# SCH_Piano_touch_sensor_2021-10-13.net
KiCad netlist of a schematic drawn in EasyEDA
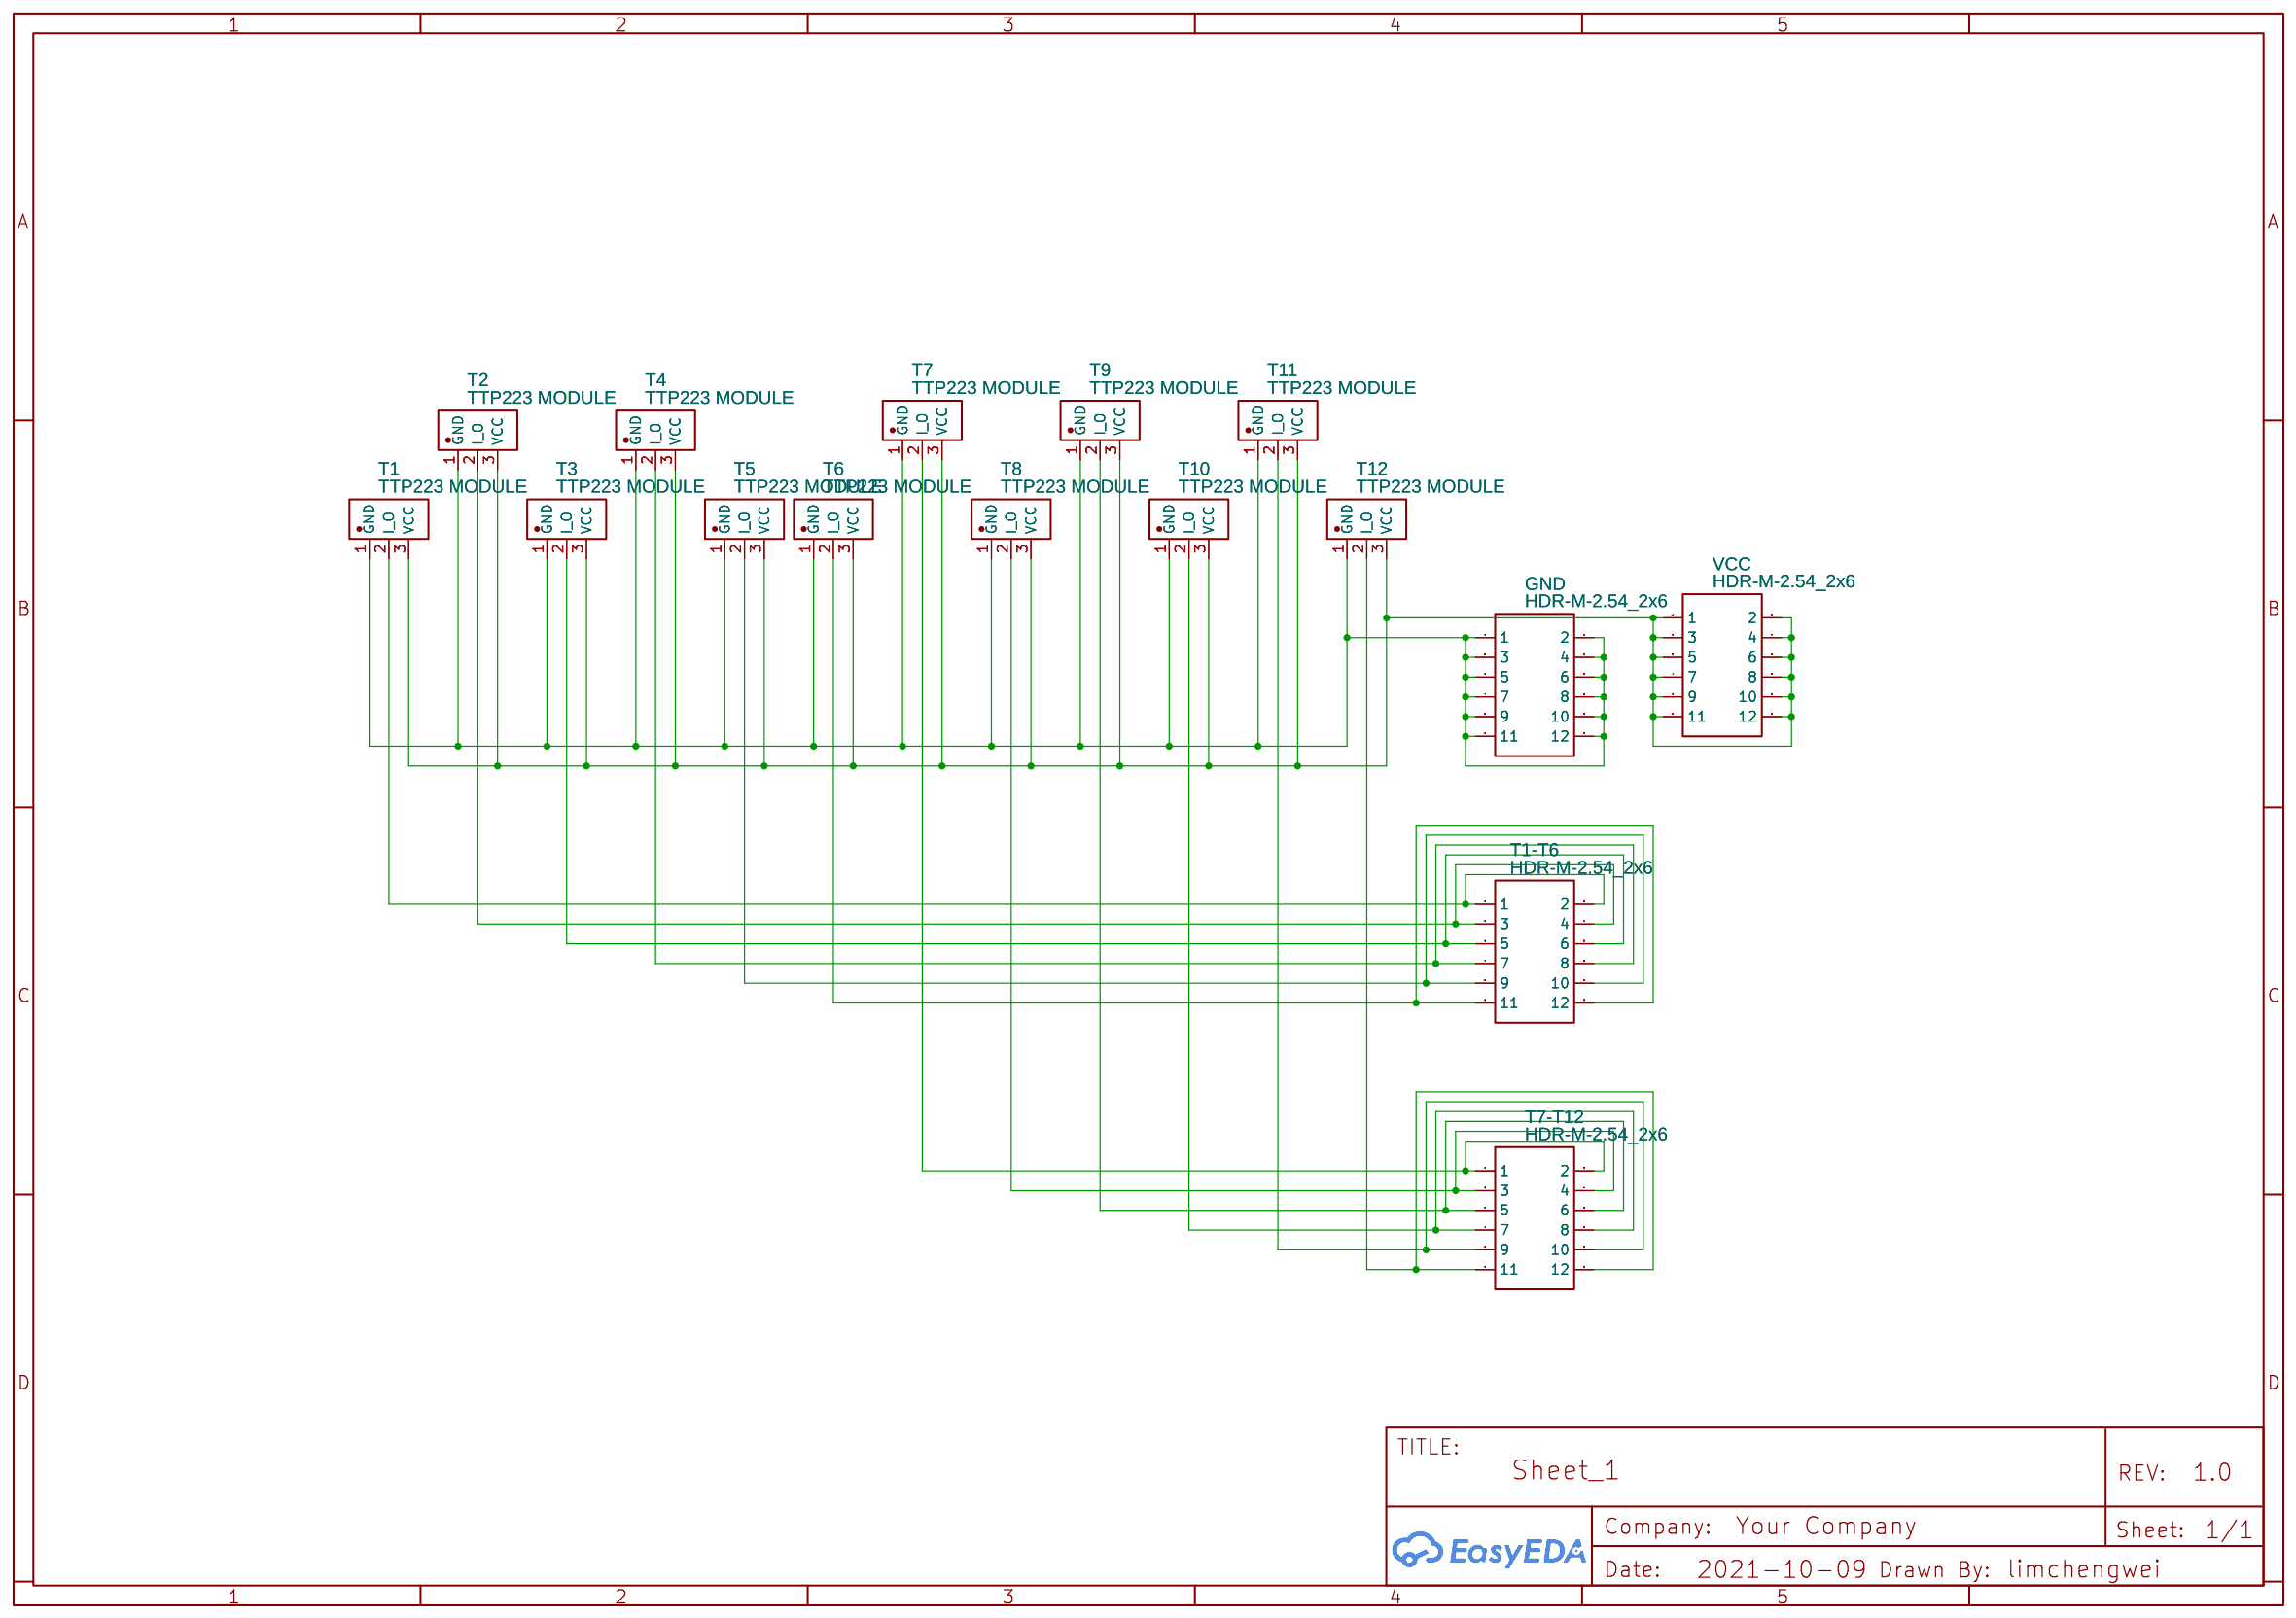
[diagram p0: schematic sheet]

(export (version "E")
  (design (tool "Eeschema 10.0.6"))
  (components
    (comp (ref "GND")
      (value "HDR-M-2.54_2x6")
      (fields (field (name "BOM_Supplier Part") "C124388"))
      (libsource (lib "") (part "HDR-M-2.54_2x6_3"))
    )
    (comp (ref "T1")
      (value "TTP223 MODULE")
      (fields
        (field (name "BOM_Manufacturer Part") "WJ2EDGVC-5.08-3P")
        (field (name "BOM_Supplier Part") "C8430")
      )
      (libsource (lib "") (part "TTP223 MODULE"))
    )
    (comp (ref "T1-T6")
      (value "HDR-M-2.54_2x6")
      (fields (field (name "BOM_Supplier Part") "C124388"))
      (libsource (lib "") (part "HDR-M-2.54_2x6_2"))
    )
    (comp (ref "T2")
      (value "TTP223 MODULE")
      (fields
        (field (name "BOM_Manufacturer Part") "WJ2EDGVC-5.08-3P")
        (field (name "BOM_Supplier Part") "C8430")
      )
      (libsource (lib "") (part "TTP223 MODULE"))
    )
    (comp (ref "T3")
      (value "TTP223 MODULE")
      (fields
        (field (name "BOM_Manufacturer Part") "WJ2EDGVC-5.08-3P")
        (field (name "BOM_Supplier Part") "C8430")
      )
      (libsource (lib "") (part "TTP223 MODULE"))
    )
    (comp (ref "T4")
      (value "TTP223 MODULE")
      (fields
        (field (name "BOM_Manufacturer Part") "WJ2EDGVC-5.08-3P")
        (field (name "BOM_Supplier Part") "C8430")
      )
      (libsource (lib "") (part "TTP223 MODULE"))
    )
    (comp (ref "T5")
      (value "TTP223 MODULE")
      (fields
        (field (name "BOM_Manufacturer Part") "WJ2EDGVC-5.08-3P")
        (field (name "BOM_Supplier Part") "C8430")
      )
      (libsource (lib "") (part "TTP223 MODULE"))
    )
    (comp (ref "T6")
      (value "TTP223 MODULE")
      (fields
        (field (name "BOM_Manufacturer Part") "WJ2EDGVC-5.08-3P")
        (field (name "BOM_Supplier Part") "C8430")
      )
      (libsource (lib "") (part "TTP223 MODULE"))
    )
    (comp (ref "T7")
      (value "TTP223 MODULE")
      (fields
        (field (name "BOM_Manufacturer Part") "WJ2EDGVC-5.08-3P")
        (field (name "BOM_Supplier Part") "C8430")
      )
      (libsource (lib "") (part "TTP223 MODULE"))
    )
    (comp (ref "T7-T12")
      (value "HDR-M-2.54_2x6")
      (fields (field (name "BOM_Supplier Part") "C124388"))
      (libsource (lib "") (part "HDR-M-2.54_2x6"))
    )
    (comp (ref "T8")
      (value "TTP223 MODULE")
      (fields
        (field (name "BOM_Manufacturer Part") "WJ2EDGVC-5.08-3P")
        (field (name "BOM_Supplier Part") "C8430")
      )
      (libsource (lib "") (part "TTP223 MODULE"))
    )
    (comp (ref "T9")
      (value "TTP223 MODULE")
      (fields
        (field (name "BOM_Manufacturer Part") "WJ2EDGVC-5.08-3P")
        (field (name "BOM_Supplier Part") "C8430")
      )
      (libsource (lib "") (part "TTP223 MODULE"))
    )
    (comp (ref "T10")
      (value "TTP223 MODULE")
      (fields
        (field (name "BOM_Manufacturer Part") "WJ2EDGVC-5.08-3P")
        (field (name "BOM_Supplier Part") "C8430")
      )
      (libsource (lib "") (part "TTP223 MODULE"))
    )
    (comp (ref "T11")
      (value "TTP223 MODULE")
      (fields
        (field (name "BOM_Manufacturer Part") "WJ2EDGVC-5.08-3P")
        (field (name "BOM_Supplier Part") "C8430")
      )
      (libsource (lib "") (part "TTP223 MODULE"))
    )
    (comp (ref "T12")
      (value "TTP223 MODULE")
      (fields
        (field (name "BOM_Manufacturer Part") "WJ2EDGVC-5.08-3P")
        (field (name "BOM_Supplier Part") "C8430")
      )
      (libsource (lib "") (part "TTP223 MODULE"))
    )
    (comp (ref "VCC")
      (value "HDR-M-2.54_2x6")
      (fields (field (name "BOM_Supplier Part") "C124388"))
      (libsource (lib "") (part "HDR-M-2.54_2x6_1"))
    )
  )
  (nets
    (net (code "1") (name "Net-(T1-GND)") (class "Default")
      (node (ref "GND") (pin "1") (pinfunction "1_1") (pintype "unspecified"))
      (node (ref "GND") (pin "10") (pinfunction "10_10") (pintype "unspecified"))
      (node (ref "GND") (pin "11") (pinfunction "11_11") (pintype "unspecified"))
      (node (ref "GND") (pin "12") (pinfunction "12_12") (pintype "unspecified"))
      (node (ref "GND") (pin "2") (pinfunction "2_2") (pintype "unspecified"))
      (node (ref "GND") (pin "3") (pinfunction "3_3") (pintype "unspecified"))
      (node (ref "GND") (pin "4") (pinfunction "4_4") (pintype "unspecified"))
      (node (ref "GND") (pin "5") (pinfunction "5_5") (pintype "unspecified"))
      (node (ref "GND") (pin "6") (pinfunction "6_6") (pintype "unspecified"))
      (node (ref "GND") (pin "7") (pinfunction "7_7") (pintype "unspecified"))
      (node (ref "GND") (pin "8") (pinfunction "8_8") (pintype "unspecified"))
      (node (ref "GND") (pin "9") (pinfunction "9_9") (pintype "unspecified"))
      (node (ref "T1") (pin "1") (pinfunction "GND_1") (pintype "unspecified"))
      (node (ref "T10") (pin "1") (pinfunction "GND_1") (pintype "unspecified"))
      (node (ref "T11") (pin "1") (pinfunction "GND_1") (pintype "unspecified"))
      (node (ref "T12") (pin "1") (pinfunction "GND_1") (pintype "unspecified"))
      (node (ref "T2") (pin "1") (pinfunction "GND_1") (pintype "unspecified"))
      (node (ref "T3") (pin "1") (pinfunction "GND_1") (pintype "unspecified"))
      (node (ref "T4") (pin "1") (pinfunction "GND_1") (pintype "unspecified"))
      (node (ref "T5") (pin "1") (pinfunction "GND_1") (pintype "unspecified"))
      (node (ref "T6") (pin "1") (pinfunction "GND_1") (pintype "unspecified"))
      (node (ref "T7") (pin "1") (pinfunction "GND_1") (pintype "unspecified"))
      (node (ref "T8") (pin "1") (pinfunction "GND_1") (pintype "unspecified"))
      (node (ref "T9") (pin "1") (pinfunction "GND_1") (pintype "unspecified"))
    )
    (net (code "2") (name "Net-(T1-I_O)") (class "Default")
      (node (ref "T1") (pin "2") (pinfunction "I_O_2") (pintype "unspecified"))
      (node (ref "T1-T6") (pin "1") (pinfunction "1_1") (pintype "unspecified"))
      (node (ref "T1-T6") (pin "2") (pinfunction "2_2") (pintype "unspecified"))
    )
    (net (code "3") (name "Net-(T1-VCC)") (class "Default")
      (node (ref "T1") (pin "3") (pinfunction "VCC_3") (pintype "unspecified"))
      (node (ref "T10") (pin "3") (pinfunction "VCC_3") (pintype "unspecified"))
      (node (ref "T11") (pin "3") (pinfunction "VCC_3") (pintype "unspecified"))
      (node (ref "T12") (pin "3") (pinfunction "VCC_3") (pintype "unspecified"))
      (node (ref "T2") (pin "3") (pinfunction "VCC_3") (pintype "unspecified"))
      (node (ref "T3") (pin "3") (pinfunction "VCC_3") (pintype "unspecified"))
      (node (ref "T4") (pin "3") (pinfunction "VCC_3") (pintype "unspecified"))
      (node (ref "T5") (pin "3") (pinfunction "VCC_3") (pintype "unspecified"))
      (node (ref "T6") (pin "3") (pinfunction "VCC_3") (pintype "unspecified"))
      (node (ref "T7") (pin "3") (pinfunction "VCC_3") (pintype "unspecified"))
      (node (ref "T8") (pin "3") (pinfunction "VCC_3") (pintype "unspecified"))
      (node (ref "T9") (pin "3") (pinfunction "VCC_3") (pintype "unspecified"))
      (node (ref "VCC") (pin "1") (pinfunction "1_1") (pintype "unspecified"))
      (node (ref "VCC") (pin "10") (pinfunction "10_10") (pintype "unspecified"))
      (node (ref "VCC") (pin "11") (pinfunction "11_11") (pintype "unspecified"))
      (node (ref "VCC") (pin "12") (pinfunction "12_12") (pintype "unspecified"))
      (node (ref "VCC") (pin "2") (pinfunction "2_2") (pintype "unspecified"))
      (node (ref "VCC") (pin "3") (pinfunction "3_3") (pintype "unspecified"))
      (node (ref "VCC") (pin "4") (pinfunction "4_4") (pintype "unspecified"))
      (node (ref "VCC") (pin "5") (pinfunction "5_5") (pintype "unspecified"))
      (node (ref "VCC") (pin "6") (pinfunction "6_6") (pintype "unspecified"))
      (node (ref "VCC") (pin "7") (pinfunction "7_7") (pintype "unspecified"))
      (node (ref "VCC") (pin "8") (pinfunction "8_8") (pintype "unspecified"))
      (node (ref "VCC") (pin "9") (pinfunction "9_9") (pintype "unspecified"))
    )
    (net (code "4") (name "Net-(T2-I_O)") (class "Default")
      (node (ref "T1-T6") (pin "3") (pinfunction "3_3") (pintype "unspecified"))
      (node (ref "T1-T6") (pin "4") (pinfunction "4_4") (pintype "unspecified"))
      (node (ref "T2") (pin "2") (pinfunction "I_O_2") (pintype "unspecified"))
    )
    (net (code "5") (name "Net-(T3-I_O)") (class "Default")
      (node (ref "T1-T6") (pin "5") (pinfunction "5_5") (pintype "unspecified"))
      (node (ref "T1-T6") (pin "6") (pinfunction "6_6") (pintype "unspecified"))
      (node (ref "T3") (pin "2") (pinfunction "I_O_2") (pintype "unspecified"))
    )
    (net (code "6") (name "Net-(T4-I_O)") (class "Default")
      (node (ref "T1-T6") (pin "7") (pinfunction "7_7") (pintype "unspecified"))
      (node (ref "T1-T6") (pin "8") (pinfunction "8_8") (pintype "unspecified"))
      (node (ref "T4") (pin "2") (pinfunction "I_O_2") (pintype "unspecified"))
    )
    (net (code "7") (name "Net-(T5-I_O)") (class "Default")
      (node (ref "T1-T6") (pin "10") (pinfunction "10_10") (pintype "unspecified"))
      (node (ref "T1-T6") (pin "9") (pinfunction "9_9") (pintype "unspecified"))
      (node (ref "T5") (pin "2") (pinfunction "I_O_2") (pintype "unspecified"))
    )
    (net (code "8") (name "Net-(T6-I_O)") (class "Default")
      (node (ref "T1-T6") (pin "11") (pinfunction "11_11") (pintype "unspecified"))
      (node (ref "T1-T6") (pin "12") (pinfunction "12_12") (pintype "unspecified"))
      (node (ref "T6") (pin "2") (pinfunction "I_O_2") (pintype "unspecified"))
    )
    (net (code "9") (name "Net-(T7-I_O)") (class "Default")
      (node (ref "T7") (pin "2") (pinfunction "I_O_2") (pintype "unspecified"))
      (node (ref "T7-T12") (pin "1") (pinfunction "1_1") (pintype "unspecified"))
      (node (ref "T7-T12") (pin "2") (pinfunction "2_2") (pintype "unspecified"))
    )
    (net (code "10") (name "Net-(T8-I_O)") (class "Default")
      (node (ref "T7-T12") (pin "3") (pinfunction "3_3") (pintype "unspecified"))
      (node (ref "T7-T12") (pin "4") (pinfunction "4_4") (pintype "unspecified"))
      (node (ref "T8") (pin "2") (pinfunction "I_O_2") (pintype "unspecified"))
    )
    (net (code "11") (name "Net-(T9-I_O)") (class "Default")
      (node (ref "T7-T12") (pin "5") (pinfunction "5_5") (pintype "unspecified"))
      (node (ref "T7-T12") (pin "6") (pinfunction "6_6") (pintype "unspecified"))
      (node (ref "T9") (pin "2") (pinfunction "I_O_2") (pintype "unspecified"))
    )
    (net (code "12") (name "Net-(T10-I_O)") (class "Default")
      (node (ref "T10") (pin "2") (pinfunction "I_O_2") (pintype "unspecified"))
      (node (ref "T7-T12") (pin "7") (pinfunction "7_7") (pintype "unspecified"))
      (node (ref "T7-T12") (pin "8") (pinfunction "8_8") (pintype "unspecified"))
    )
    (net (code "13") (name "Net-(T11-I_O)") (class "Default")
      (node (ref "T11") (pin "2") (pinfunction "I_O_2") (pintype "unspecified"))
      (node (ref "T7-T12") (pin "10") (pinfunction "10_10") (pintype "unspecified"))
      (node (ref "T7-T12") (pin "9") (pinfunction "9_9") (pintype "unspecified"))
    )
    (net (code "14") (name "Net-(T12-I_O)") (class "Default")
      (node (ref "T12") (pin "2") (pinfunction "I_O_2") (pintype "unspecified"))
      (node (ref "T7-T12") (pin "11") (pinfunction "11_11") (pintype "unspecified"))
      (node (ref "T7-T12") (pin "12") (pinfunction "12_12") (pintype "unspecified"))
    )
  )
)
